# CPU_GPIOG_I_VDD.net
KiCad netlist of a schematic drawn in Altium Designer
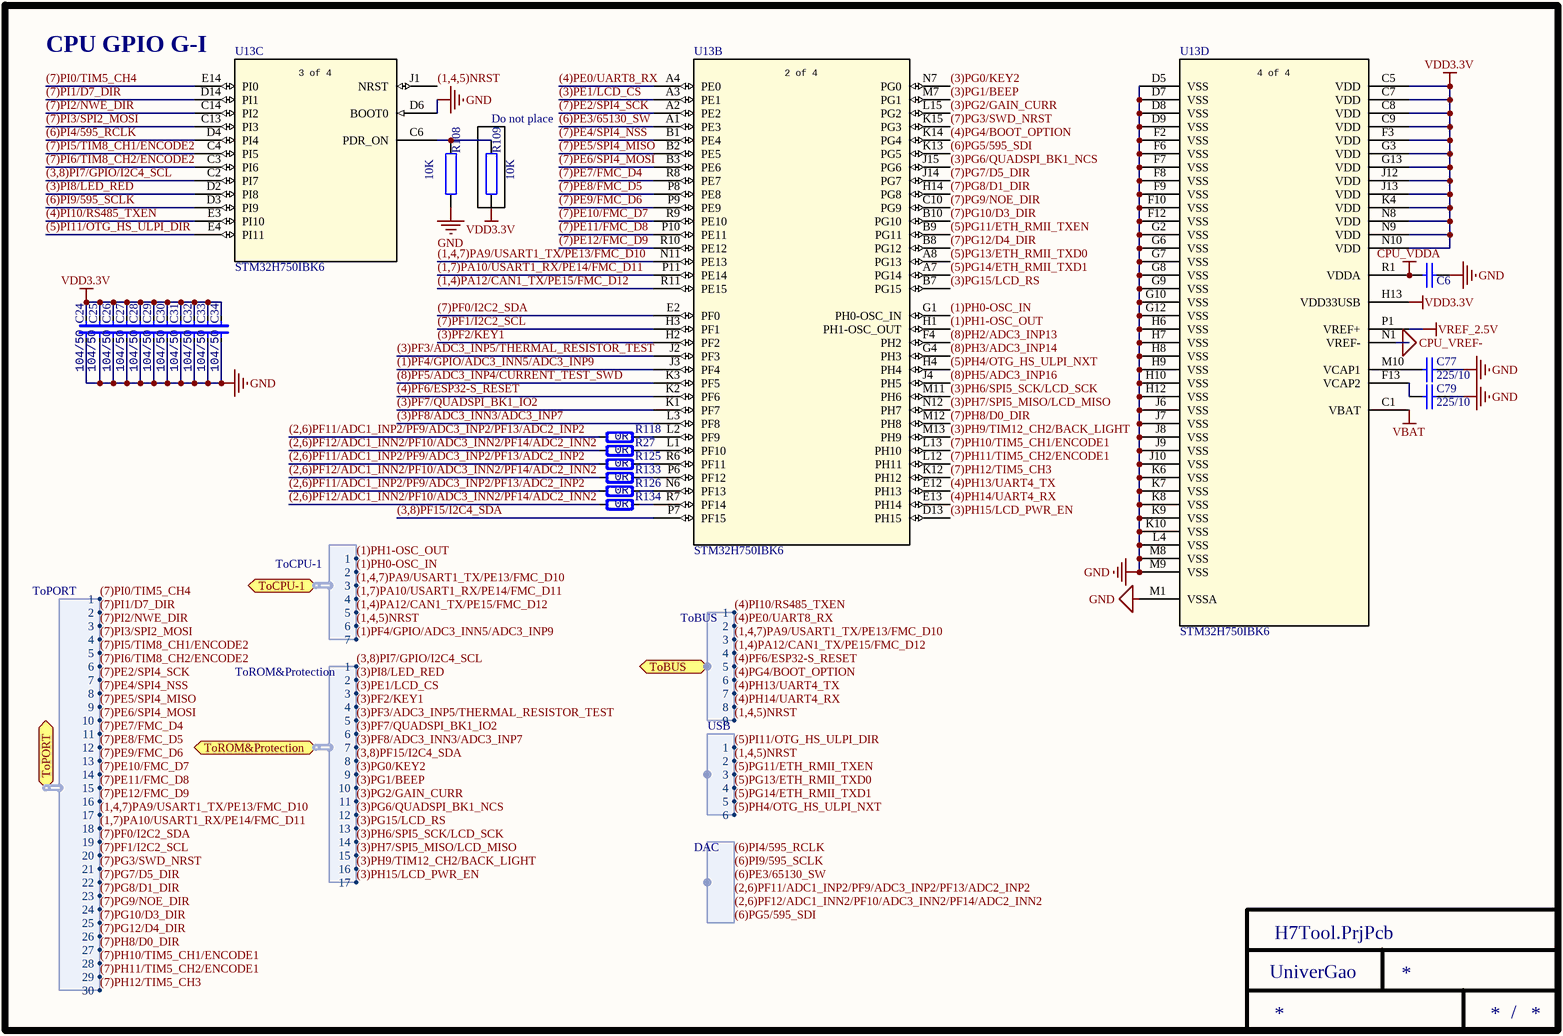
[diagram p0: CPU_GPIOG_I_VDD.SchDoc]

(export (version "E")
  (design (tool "Eeschema 10.0.6"))
  (components
    (comp (ref "C6") (value "104/50") (footprint "0603") (libsource (lib "电容") (part "CAP1")))
    (comp (ref "C24")
      (value "104/50")
      (footprint "PCB_PassiveCap:CAP_0603")
      (description "Capacitor")
      (fields (field (name "Comment") "C0603"))
      (libsource (lib "SCH_Passive") (part "Cap_0603"))
    )
    (comp (ref "C25")
      (value "104/50")
      (footprint "PCB_PassiveCap:CAP_0603")
      (description "Capacitor")
      (fields (field (name "Comment") "C0603"))
      (libsource (lib "SCH_Passive") (part "Cap_0603"))
    )
    (comp (ref "C26")
      (value "104/50")
      (footprint "PCB_PassiveCap:CAP_0603")
      (description "Capacitor")
      (fields (field (name "Comment") "C0603"))
      (libsource (lib "SCH_Passive") (part "Cap_0603"))
    )
    (comp (ref "C27")
      (value "104/50")
      (footprint "PCB_PassiveCap:CAP_0603")
      (description "Capacitor")
      (fields (field (name "Comment") "C0603"))
      (libsource (lib "SCH_Passive") (part "Cap_0603"))
    )
    (comp (ref "C28")
      (value "104/50")
      (footprint "PCB_PassiveCap:CAP_0603")
      (description "Capacitor")
      (fields (field (name "Comment") "C0603"))
      (libsource (lib "SCH_Passive") (part "Cap_0603"))
    )
    (comp (ref "C29")
      (value "104/50")
      (footprint "PCB_PassiveCap:CAP_0603")
      (description "Capacitor")
      (fields (field (name "Comment") "C0603"))
      (libsource (lib "SCH_Passive") (part "Cap_0603"))
    )
    (comp (ref "C30")
      (value "104/50")
      (footprint "PCB_PassiveCap:CAP_0603")
      (description "Capacitor")
      (fields (field (name "Comment") "C0603"))
      (libsource (lib "SCH_Passive") (part "Cap_0603"))
    )
    (comp (ref "C31")
      (value "104/50")
      (footprint "PCB_PassiveCap:CAP_0603")
      (description "Capacitor")
      (fields (field (name "Comment") "C0603"))
      (libsource (lib "SCH_Passive") (part "Cap_0603"))
    )
    (comp (ref "C32")
      (value "104/50")
      (footprint "PCB_PassiveCap:CAP_0603")
      (description "Capacitor")
      (fields (field (name "Comment") "C0603"))
      (libsource (lib "SCH_Passive") (part "Cap_0603"))
    )
    (comp (ref "C33")
      (value "104/50")
      (footprint "PCB_PassiveCap:CAP_0603")
      (description "Capacitor")
      (fields (field (name "Comment") "C0603"))
      (libsource (lib "SCH_Passive") (part "Cap_0603"))
    )
    (comp (ref "C34")
      (value "104/50")
      (footprint "PCB_PassiveCap:CAP_0603")
      (description "Capacitor")
      (fields (field (name "Comment") "C0603"))
      (libsource (lib "SCH_Passive") (part "Cap_0603"))
    )
    (comp (ref "C77") (value "225/10") (footprint "0603") (libsource (lib "电容") (part "CAP1")))
    (comp (ref "C79") (value "225/10") (footprint "0603") (libsource (lib "电容") (part "CAP1")))
    (comp (ref "R27")
      (value "0R")
      (footprint "PCB_PassiveRes:RES_0603")
      (description "Resistor")
      (fields (field (name "Comment") "R0603"))
      (libsource (lib "SCH_Passive") (part "Res_0603"))
    )
    (comp (ref "R108") (value "10K") (footprint "0603") (libsource (lib "电阻") (part "RES")))
    (comp (ref "R109")
      (value "10K")
      (footprint "0603")
      (description "10K(Do not place)")
      (libsource (lib "电阻") (part "RES"))
    )
    (comp (ref "R118")
      (value "0R")
      (footprint "PCB_PassiveRes:RES_0603")
      (description "Resistor")
      (fields (field (name "Comment") "R0603"))
      (libsource (lib "SCH_Passive") (part "Res_0603"))
    )
    (comp (ref "R125")
      (value "0R")
      (footprint "PCB_PassiveRes:RES_0603")
      (description "Resistor")
      (fields (field (name "Comment") "R0603"))
      (libsource (lib "SCH_Passive") (part "Res_0603"))
    )
    (comp (ref "R126")
      (value "0R")
      (footprint "PCB_PassiveRes:RES_0603")
      (description "Resistor")
      (fields (field (name "Comment") "R0603"))
      (libsource (lib "SCH_Passive") (part "Res_0603"))
    )
    (comp (ref "R133")
      (value "0R")
      (footprint "PCB_PassiveRes:RES_0603")
      (description "Resistor")
      (fields (field (name "Comment") "R0603"))
      (libsource (lib "SCH_Passive") (part "Res_0603"))
    )
    (comp (ref "R134")
      (value "0R")
      (footprint "PCB_PassiveRes:RES_0603")
      (description "Resistor")
      (fields (field (name "Comment") "R0603"))
      (libsource (lib "SCH_Passive") (part "Res_0603"))
    )
    (comp (ref "U13")
      (value "STM32H750IBK6")
      (footprint "UFBGA 10X10 P 0.65 176+25")
      (description "No Description Available")
      (fields (field (name "COPYRIGHT") "Copyright (C) 2022 Ultra Librarian. All rights reserved."))
      (libsource (lib "STM32H750IBK6") (part "STM32H750IBK6"))
    )
  )
  (nets
    (net (code "5") (name "/(1)PF4{slash}GPIO{slash}ADC3_INN5{slash}ADC3_INP9") (class "Default")
      (node (ref "U13") (pin "J3") (pinfunction "PF4_J3") (pintype "bidirectional"))
    )
    (net (code "6") (name "/(1)PH0-OSC_IN") (class "Default")
      (node (ref "U13") (pin "G1") (pinfunction "PH0-OSC_IN_G1") (pintype "bidirectional"))
    )
    (net (code "7") (name "/(1)PH1-OSC_OUT") (class "Default")
      (node (ref "U13") (pin "H1") (pinfunction "PH1-OSC_OUT_H1") (pintype "bidirectional"))
    )
    (net (code "8") (name "/(1,4)PA12{slash}CAN1_TX{slash}PE15{slash}FMC_D12") (class "Default")
      (node (ref "U13") (pin "R11") (pinfunction "PE15_R11") (pintype "bidirectional"))
    )
    (net (code "9") (name "/(1,4,5)NRST") (class "Default")
      (node (ref "U13") (pin "J1") (pinfunction "NRST_J1") (pintype "bidirectional"))
    )
    (net (code "10") (name "/(1,4,7)PA9{slash}USART1_TX{slash}PE13{slash}FMC_D10") (class "Default")
      (node (ref "U13") (pin "N11") (pinfunction "PE13_N11") (pintype "bidirectional"))
    )
    (net (code "11") (name "/(1,7)PA10{slash}USART1_RX{slash}PE14{slash}FMC_D11") (class "Default")
      (node (ref "U13") (pin "P11") (pinfunction "PE14_P11") (pintype "bidirectional"))
    )
    (net (code "12") (name "/(2,6)PF11{slash}ADC1_INP2{slash}PF9{slash}ADC3_INP2{slash}PF13{slash}ADC2_INP2") (class "Default")
      (node (ref "R118") (pin "1") (pinfunction "1_1") (pintype "passive"))
      (node (ref "R125") (pin "1") (pinfunction "1_1") (pintype "passive"))
      (node (ref "R126") (pin "1") (pinfunction "1_1") (pintype "passive"))
    )
    (net (code "13") (name "/(2,6)PF12{slash}ADC1_INN2{slash}PF10{slash}ADC3_INN2{slash}PF14{slash}ADC2_INN2") (class "Default")
      (node (ref "R133") (pin "1") (pinfunction "1_1") (pintype "passive"))
      (node (ref "R134") (pin "1") (pinfunction "1_1") (pintype "passive"))
      (node (ref "R27") (pin "1") (pinfunction "1_1") (pintype "passive"))
    )
    (net (code "14") (name "/(3)PE1{slash}LCD_CS") (class "Default")
      (node (ref "U13") (pin "A3") (pinfunction "PE1_A3") (pintype "bidirectional"))
    )
    (net (code "15") (name "/(3)PF2{slash}KEY1") (class "Default")
      (node (ref "U13") (pin "H2") (pinfunction "PF2_H2") (pintype "bidirectional"))
    )
    (net (code "16") (name "/(3)PF3{slash}ADC3_INP5{slash}THERMAL_RESISTOR_TEST") (class "Default")
      (node (ref "U13") (pin "J2") (pinfunction "PF3_J2") (pintype "bidirectional"))
    )
    (net (code "17") (name "/(3)PF7{slash}QUADSPI_BK1_IO2") (class "Default")
      (node (ref "U13") (pin "K1") (pinfunction "PF7_K1") (pintype "bidirectional"))
    )
    (net (code "18") (name "/(3)PF8{slash}ADC3_INN3{slash}ADC3_INP7") (class "Default")
      (node (ref "U13") (pin "L3") (pinfunction "PF8_L3") (pintype "bidirectional"))
    )
    (net (code "19") (name "/(3)PG0{slash}KEY2") (class "Default")
      (node (ref "U13") (pin "N7") (pinfunction "PG0_N7") (pintype "bidirectional"))
    )
    (net (code "20") (name "/(3)PG1{slash}BEEP") (class "Default")
      (node (ref "U13") (pin "M7") (pinfunction "PG1_M7") (pintype "bidirectional"))
    )
    (net (code "21") (name "/(3)PG2{slash}GAIN_CURR") (class "Default")
      (node (ref "U13") (pin "L15") (pinfunction "PG2_L15") (pintype "bidirectional"))
    )
    (net (code "22") (name "/(3)PG6{slash}QUADSPI_BK1_NCS") (class "Default")
      (node (ref "U13") (pin "J15") (pinfunction "PG6_J15") (pintype "bidirectional"))
    )
    (net (code "23") (name "/(3)PG15{slash}LCD_RS") (class "Default")
      (node (ref "U13") (pin "B7") (pinfunction "PG15_B7") (pintype "bidirectional"))
    )
    (net (code "24") (name "/(3)PH6{slash}SPI5_SCK{slash}LCD_SCK") (class "Default")
      (node (ref "U13") (pin "M11") (pinfunction "PH6_M11") (pintype "bidirectional"))
    )
    (net (code "25") (name "/(3)PH7{slash}SPI5_MISO{slash}LCD_MISO") (class "Default")
      (node (ref "U13") (pin "N12") (pinfunction "PH7_N12") (pintype "bidirectional"))
    )
    (net (code "26") (name "/(3)PH9{slash}TIM12_CH2{slash}BACK_LIGHT") (class "Default")
      (node (ref "U13") (pin "M13") (pinfunction "PH9_M13") (pintype "bidirectional"))
    )
    (net (code "27") (name "/(3)PH15{slash}LCD_PWR_EN") (class "Default")
      (node (ref "U13") (pin "D13") (pinfunction "PH15_D13") (pintype "bidirectional"))
    )
    (net (code "28") (name "/(3)PI8{slash}LED_RED") (class "Default")
      (node (ref "U13") (pin "D2") (pinfunction "PI8_D2") (pintype "bidirectional"))
    )
    (net (code "29") (name "/(3,8)PF15{slash}I2C4_SDA") (class "Default")
      (node (ref "U13") (pin "P7") (pinfunction "PF15_P7") (pintype "bidirectional"))
    )
    (net (code "30") (name "/(3,8)PI7{slash}GPIO{slash}I2C4_SCL") (class "Default")
      (node (ref "U13") (pin "C2") (pinfunction "PI7_C2") (pintype "bidirectional"))
    )
    (net (code "31") (name "/(4)PE0{slash}UART8_RX") (class "Default")
      (node (ref "U13") (pin "A4") (pinfunction "PE0_A4") (pintype "bidirectional"))
    )
    (net (code "32") (name "/(4)PF6{slash}ESP32-S_RESET") (class "Default")
      (node (ref "U13") (pin "K2") (pinfunction "PF6_K2") (pintype "bidirectional"))
    )
    (net (code "33") (name "/(4)PG4{slash}BOOT_OPTION") (class "Default")
      (node (ref "U13") (pin "K14") (pinfunction "PG4_K14") (pintype "bidirectional"))
    )
    (net (code "34") (name "/(4)PH13{slash}UART4_TX") (class "Default")
      (node (ref "U13") (pin "E12") (pinfunction "PH13_E12") (pintype "bidirectional"))
    )
    (net (code "35") (name "/(4)PH14{slash}UART4_RX") (class "Default")
      (node (ref "U13") (pin "E13") (pinfunction "PH14_E13") (pintype "bidirectional"))
    )
    (net (code "36") (name "/(4)PI10{slash}RS485_TXEN") (class "Default")
      (node (ref "U13") (pin "E3") (pinfunction "PI10_E3") (pintype "bidirectional"))
    )
    (net (code "37") (name "/(5)PG11{slash}ETH_RMII_TXEN") (class "Default")
      (node (ref "U13") (pin "B9") (pinfunction "PG11_B9") (pintype "bidirectional"))
    )
    (net (code "38") (name "/(5)PG13{slash}ETH_RMII_TXD0") (class "Default")
      (node (ref "U13") (pin "A8") (pinfunction "PG13_A8") (pintype "bidirectional"))
    )
    (net (code "39") (name "/(5)PG14{slash}ETH_RMII_TXD1") (class "Default")
      (node (ref "U13") (pin "A7") (pinfunction "PG14_A7") (pintype "bidirectional"))
    )
    (net (code "40") (name "/(5)PH4{slash}OTG_HS_ULPI_NXT") (class "Default")
      (node (ref "U13") (pin "H4") (pinfunction "PH4_H4") (pintype "bidirectional"))
    )
    (net (code "41") (name "/(5)PI11{slash}OTG_HS_ULPI_DIR") (class "Default")
      (node (ref "U13") (pin "E4") (pinfunction "PI11_E4") (pintype "bidirectional"))
    )
    (net (code "42") (name "/(6)PE3{slash}65130_SW") (class "Default")
      (node (ref "U13") (pin "A1") (pinfunction "PE3_A1") (pintype "bidirectional"))
    )
    (net (code "43") (name "/(6)PG5{slash}595_SDI") (class "Default")
      (node (ref "U13") (pin "K13") (pinfunction "PG5_K13") (pintype "bidirectional"))
    )
    (net (code "44") (name "/(6)PI4{slash}595_RCLK") (class "Default")
      (node (ref "U13") (pin "D4") (pinfunction "PI4_D4") (pintype "bidirectional"))
    )
    (net (code "45") (name "/(6)PI9{slash}595_SCLK") (class "Default")
      (node (ref "U13") (pin "D3") (pinfunction "PI9_D3") (pintype "bidirectional"))
    )
    (net (code "46") (name "/(7)PE2{slash}SPI4_SCK") (class "Default")
      (node (ref "U13") (pin "A2") (pinfunction "PE2_A2") (pintype "bidirectional"))
    )
    (net (code "47") (name "/(7)PE4{slash}SPI4_NSS") (class "Default")
      (node (ref "U13") (pin "B1") (pinfunction "PE4_B1") (pintype "bidirectional"))
    )
    (net (code "48") (name "/(7)PE5{slash}SPI4_MISO") (class "Default")
      (node (ref "U13") (pin "B2") (pinfunction "PE5_B2") (pintype "bidirectional"))
    )
    (net (code "49") (name "/(7)PE6{slash}SPI4_MOSI") (class "Default")
      (node (ref "U13") (pin "B3") (pinfunction "PE6_B3") (pintype "bidirectional"))
    )
    (net (code "50") (name "/(7)PE7{slash}FMC_D4") (class "Default")
      (node (ref "U13") (pin "R8") (pinfunction "PE7_R8") (pintype "bidirectional"))
    )
    (net (code "51") (name "/(7)PE8{slash}FMC_D5") (class "Default")
      (node (ref "U13") (pin "P8") (pinfunction "PE8_P8") (pintype "bidirectional"))
    )
    (net (code "52") (name "/(7)PE9{slash}FMC_D6") (class "Default")
      (node (ref "U13") (pin "P9") (pinfunction "PE9_P9") (pintype "bidirectional"))
    )
    (net (code "53") (name "/(7)PE10{slash}FMC_D7") (class "Default")
      (node (ref "U13") (pin "R9") (pinfunction "PE10_R9") (pintype "bidirectional"))
    )
    (net (code "54") (name "/(7)PE11{slash}FMC_D8") (class "Default")
      (node (ref "U13") (pin "P10") (pinfunction "PE11_P10") (pintype "bidirectional"))
    )
    (net (code "55") (name "/(7)PE12{slash}FMC_D9") (class "Default")
      (node (ref "U13") (pin "R10") (pinfunction "PE12_R10") (pintype "bidirectional"))
    )
    (net (code "56") (name "/(7)PF0{slash}I2C2_SDA") (class "Default")
      (node (ref "U13") (pin "E2") (pinfunction "PF0_E2") (pintype "bidirectional"))
    )
    (net (code "57") (name "/(7)PF1{slash}I2C2_SCL") (class "Default")
      (node (ref "U13") (pin "H3") (pinfunction "PF1_H3") (pintype "bidirectional"))
    )
    (net (code "58") (name "/(7)PG3{slash}SWD_NRST") (class "Default")
      (node (ref "U13") (pin "K15") (pinfunction "PG3_K15") (pintype "bidirectional"))
    )
    (net (code "59") (name "/(7)PG7{slash}D5_DIR") (class "Default")
      (node (ref "U13") (pin "J14") (pinfunction "PG7_J14") (pintype "bidirectional"))
    )
    (net (code "60") (name "/(7)PG8{slash}D1_DIR") (class "Default")
      (node (ref "U13") (pin "H14") (pinfunction "PG8_H14") (pintype "bidirectional"))
    )
    (net (code "61") (name "/(7)PG9{slash}NOE_DIR") (class "Default")
      (node (ref "U13") (pin "C10") (pinfunction "PG9_C10") (pintype "bidirectional"))
    )
    (net (code "62") (name "/(7)PG10{slash}D3_DIR") (class "Default")
      (node (ref "U13") (pin "B10") (pinfunction "PG10_B10") (pintype "bidirectional"))
    )
    (net (code "63") (name "/(7)PG12{slash}D4_DIR") (class "Default")
      (node (ref "U13") (pin "B8") (pinfunction "PG12_B8") (pintype "bidirectional"))
    )
    (net (code "64") (name "/(7)PH8{slash}D0_DIR") (class "Default")
      (node (ref "U13") (pin "M12") (pinfunction "PH8_M12") (pintype "bidirectional"))
    )
    (net (code "65") (name "/(7)PH10{slash}TIM5_CH1{slash}ENCODE1") (class "Default")
      (node (ref "U13") (pin "L13") (pinfunction "PH10_L13") (pintype "bidirectional"))
    )
    (net (code "66") (name "/(7)PH11{slash}TIM5_CH2{slash}ENCODE1") (class "Default")
      (node (ref "U13") (pin "L12") (pinfunction "PH11_L12") (pintype "bidirectional"))
    )
    (net (code "67") (name "/(7)PH12{slash}TIM5_CH3") (class "Default")
      (node (ref "U13") (pin "K12") (pinfunction "PH12_K12") (pintype "bidirectional"))
    )
    (net (code "68") (name "/(7)PI0{slash}TIM5_CH4") (class "Default")
      (node (ref "U13") (pin "E14") (pinfunction "PI0_E14") (pintype "bidirectional"))
    )
    (net (code "69") (name "/(7)PI1{slash}D7_DIR") (class "Default")
      (node (ref "U13") (pin "D14") (pinfunction "PI1_D14") (pintype "bidirectional"))
    )
    (net (code "70") (name "/(7)PI2{slash}NWE_DIR") (class "Default")
      (node (ref "U13") (pin "C14") (pinfunction "PI2_C14") (pintype "bidirectional"))
    )
    (net (code "71") (name "/(7)PI3{slash}SPI2_MOSI") (class "Default")
      (node (ref "U13") (pin "C13") (pinfunction "PI3_C13") (pintype "bidirectional"))
    )
    (net (code "72") (name "/(7)PI5{slash}TIM8_CH1{slash}ENCODE2") (class "Default")
      (node (ref "U13") (pin "C4") (pinfunction "PI5_C4") (pintype "bidirectional"))
    )
    (net (code "73") (name "/(7)PI6{slash}TIM8_CH2{slash}ENCODE2") (class "Default")
      (node (ref "U13") (pin "C3") (pinfunction "PI6_C3") (pintype "bidirectional"))
    )
    (net (code "74") (name "/(8)PF5{slash}ADC3_INP4{slash}CURRENT_TEST_SWD") (class "Default")
      (node (ref "U13") (pin "K3") (pinfunction "PF5_K3") (pintype "bidirectional"))
    )
    (net (code "75") (name "/(8)PH2{slash}ADC3_INP13") (class "Default")
      (node (ref "U13") (pin "F4") (pinfunction "PH2_F4") (pintype "bidirectional"))
    )
    (net (code "76") (name "/(8)PH3{slash}ADC3_INP14") (class "Default")
      (node (ref "U13") (pin "G4") (pinfunction "PH3_G4") (pintype "bidirectional"))
    )
    (net (code "77") (name "/(8)PH5{slash}ADC3_INP16") (class "Default")
      (node (ref "U13") (pin "J4") (pinfunction "PH5_J4") (pintype "bidirectional"))
    )
    (net (code "82") (name "CPU_VDDA") (class "Default")
      (node (ref "C6") (pin "2") (pinfunction "2_2") (pintype "passive"))
      (node (ref "U13") (pin "R1") (pinfunction "VDDA_R1") (pintype "power_in"))
    )
    (net (code "83") (name "CPU_VREF-") (class "Default")
      (node (ref "U13") (pin "N1") (pinfunction "VREF-_N1") (pintype "power_in"))
    )
    (net (code "84") (name "GND") (class "Default")
      (node (ref "C24") (pin "1") (pinfunction "1_1") (pintype "passive"))
      (node (ref "C25") (pin "1") (pinfunction "1_1") (pintype "passive"))
      (node (ref "C26") (pin "1") (pinfunction "1_1") (pintype "passive"))
      (node (ref "C27") (pin "1") (pinfunction "1_1") (pintype "passive"))
      (node (ref "C28") (pin "1") (pinfunction "1_1") (pintype "passive"))
      (node (ref "C29") (pin "1") (pinfunction "1_1") (pintype "passive"))
      (node (ref "C30") (pin "1") (pinfunction "1_1") (pintype "passive"))
      (node (ref "C31") (pin "1") (pinfunction "1_1") (pintype "passive"))
      (node (ref "C32") (pin "1") (pinfunction "1_1") (pintype "passive"))
      (node (ref "C33") (pin "1") (pinfunction "1_1") (pintype "passive"))
      (node (ref "C34") (pin "1") (pinfunction "1_1") (pintype "passive"))
      (node (ref "C6") (pin "1") (pinfunction "1_1") (pintype "passive"))
      (node (ref "C77") (pin "1") (pinfunction "1_1") (pintype "passive"))
      (node (ref "C79") (pin "1") (pinfunction "1_1") (pintype "passive"))
      (node (ref "R108") (pin "2") (pinfunction "2_2") (pintype "passive"))
      (node (ref "U13") (pin "D5") (pinfunction "VSS_D5") (pintype "power_in"))
      (node (ref "U13") (pin "D6") (pinfunction "BOOT0_D6") (pintype "input"))
      (node (ref "U13") (pin "D7") (pinfunction "VSS_D7") (pintype "power_in"))
      (node (ref "U13") (pin "D8") (pinfunction "VSS_D8") (pintype "power_in"))
      (node (ref "U13") (pin "D9") (pinfunction "VSS_D9") (pintype "power_in"))
      (node (ref "U13") (pin "F10") (pinfunction "VSS_F10") (pintype "power_in"))
      (node (ref "U13") (pin "F12") (pinfunction "VSS_F12") (pintype "power_in"))
      (node (ref "U13") (pin "F2") (pinfunction "VSS_F2") (pintype "power_in"))
      (node (ref "U13") (pin "F6") (pinfunction "VSS_F6") (pintype "power_in"))
      (node (ref "U13") (pin "F7") (pinfunction "VSS_F7") (pintype "power_in"))
      (node (ref "U13") (pin "F8") (pinfunction "VSS_F8") (pintype "power_in"))
      (node (ref "U13") (pin "F9") (pinfunction "VSS_F9") (pintype "power_in"))
      (node (ref "U13") (pin "G10") (pinfunction "VSS_G10") (pintype "power_in"))
      (node (ref "U13") (pin "G12") (pinfunction "VSS_G12") (pintype "power_in"))
      (node (ref "U13") (pin "G2") (pinfunction "VSS_G2") (pintype "power_in"))
      (node (ref "U13") (pin "G6") (pinfunction "VSS_G6") (pintype "power_in"))
      (node (ref "U13") (pin "G7") (pinfunction "VSS_G7") (pintype "power_in"))
      (node (ref "U13") (pin "G8") (pinfunction "VSS_G8") (pintype "power_in"))
      (node (ref "U13") (pin "G9") (pinfunction "VSS_G9") (pintype "power_in"))
      (node (ref "U13") (pin "H10") (pinfunction "VSS_H10") (pintype "power_in"))
      (node (ref "U13") (pin "H12") (pinfunction "VSS_H12") (pintype "power_in"))
      (node (ref "U13") (pin "H6") (pinfunction "VSS_H6") (pintype "power_in"))
      (node (ref "U13") (pin "H7") (pinfunction "VSS_H7") (pintype "power_in"))
      (node (ref "U13") (pin "H8") (pinfunction "VSS_H8") (pintype "power_in"))
      (node (ref "U13") (pin "H9") (pinfunction "VSS_H9") (pintype "power_in"))
      (node (ref "U13") (pin "J10") (pinfunction "VSS_J10") (pintype "power_in"))
      (node (ref "U13") (pin "J6") (pinfunction "VSS_J6") (pintype "power_in"))
      (node (ref "U13") (pin "J7") (pinfunction "VSS_J7") (pintype "power_in"))
      (node (ref "U13") (pin "J8") (pinfunction "VSS_J8") (pintype "power_in"))
      (node (ref "U13") (pin "J9") (pinfunction "VSS_J9") (pintype "power_in"))
      (node (ref "U13") (pin "K10") (pinfunction "VSS_K10") (pintype "power_in"))
      (node (ref "U13") (pin "K6") (pinfunction "VSS_K6") (pintype "power_in"))
      (node (ref "U13") (pin "K7") (pinfunction "VSS_K7") (pintype "power_in"))
      (node (ref "U13") (pin "K8") (pinfunction "VSS_K8") (pintype "power_in"))
      (node (ref "U13") (pin "K9") (pinfunction "VSS_K9") (pintype "power_in"))
      (node (ref "U13") (pin "L4") (pinfunction "VSS_L4") (pintype "power_in"))
      (node (ref "U13") (pin "M1") (pinfunction "VSSA_M1") (pintype "power_in"))
      (node (ref "U13") (pin "M8") (pinfunction "VSS_M8") (pintype "power_in"))
      (node (ref "U13") (pin "M9") (pinfunction "VSS_M9") (pintype "power_in"))
    )
    (net (code "85") (name "Net-(U13B-PF9)") (class "Default")
      (node (ref "R118") (pin "2") (pinfunction "2_2") (pintype "passive"))
      (node (ref "U13") (pin "L2") (pinfunction "PF9_L2") (pintype "bidirectional"))
    )
    (net (code "86") (name "Net-(U13B-PF10)") (class "Default")
      (node (ref "R27") (pin "2") (pinfunction "2_2") (pintype "passive"))
      (node (ref "U13") (pin "L1") (pinfunction "PF10_L1") (pintype "bidirectional"))
    )
    (net (code "87") (name "Net-(U13B-PF11)") (class "Default")
      (node (ref "R125") (pin "2") (pinfunction "2_2") (pintype "passive"))
      (node (ref "U13") (pin "R6") (pinfunction "PF11_R6") (pintype "bidirectional"))
    )
    (net (code "88") (name "Net-(U13B-PF12)") (class "Default")
      (node (ref "R133") (pin "2") (pinfunction "2_2") (pintype "passive"))
      (node (ref "U13") (pin "P6") (pinfunction "PF12_P6") (pintype "bidirectional"))
    )
    (net (code "89") (name "Net-(U13B-PF13)") (class "Default")
      (node (ref "R126") (pin "2") (pinfunction "2_2") (pintype "passive"))
      (node (ref "U13") (pin "N6") (pinfunction "PF13_N6") (pintype "bidirectional"))
    )
    (net (code "90") (name "Net-(U13B-PF14)") (class "Default")
      (node (ref "R134") (pin "2") (pinfunction "2_2") (pintype "passive"))
      (node (ref "U13") (pin "R7") (pinfunction "PF14_R7") (pintype "bidirectional"))
    )
    (net (code "91") (name "Net-(U13C-PDR_ON)") (class "Default")
      (node (ref "R108") (pin "1") (pinfunction "1_1") (pintype "passive"))
      (node (ref "R109") (pin "1") (pinfunction "1_1") (pintype "passive"))
      (node (ref "U13") (pin "C6") (pinfunction "PDR_ON_C6") (pintype "passive"))
    )
    (net (code "92") (name "Net-(U13D-VCAP1)") (class "Default")
      (node (ref "C77") (pin "2") (pinfunction "2_2") (pintype "passive"))
      (node (ref "U13") (pin "M10") (pinfunction "VCAP1_M10") (pintype "power_in"))
    )
    (net (code "93") (name "Net-(U13D-VCAP2)") (class "Default")
      (node (ref "C79") (pin "2") (pinfunction "2_2") (pintype "passive"))
      (node (ref "U13") (pin "F13") (pinfunction "VCAP2_F13") (pintype "power_in"))
    )
    (net (code "94") (name "VBAT") (class "Default")
      (node (ref "U13") (pin "C1") (pinfunction "VBAT_C1") (pintype "power_in"))
    )
    (net (code "95") (name "VDD3.3V") (class "Default")
      (node (ref "C24") (pin "2") (pinfunction "2_2") (pintype "passive"))
      (node (ref "C25") (pin "2") (pinfunction "2_2") (pintype "passive"))
      (node (ref "C26") (pin "2") (pinfunction "2_2") (pintype "passive"))
      (node (ref "C27") (pin "2") (pinfunction "2_2") (pintype "passive"))
      (node (ref "C28") (pin "2") (pinfunction "2_2") (pintype "passive"))
      (node (ref "C29") (pin "2") (pinfunction "2_2") (pintype "passive"))
      (node (ref "C30") (pin "2") (pinfunction "2_2") (pintype "passive"))
      (node (ref "C31") (pin "2") (pinfunction "2_2") (pintype "passive"))
      (node (ref "C32") (pin "2") (pinfunction "2_2") (pintype "passive"))
      (node (ref "C33") (pin "2") (pinfunction "2_2") (pintype "passive"))
      (node (ref "C34") (pin "2") (pinfunction "2_2") (pintype "passive"))
      (node (ref "R109") (pin "2") (pinfunction "2_2") (pintype "passive"))
      (node (ref "U13") (pin "C5") (pinfunction "VDD_C5") (pintype "power_in"))
      (node (ref "U13") (pin "C7") (pinfunction "VDD_C7") (pintype "power_in"))
      (node (ref "U13") (pin "C8") (pinfunction "VDD_C8") (pintype "power_in"))
      (node (ref "U13") (pin "C9") (pinfunction "VDD_C9") (pintype "power_in"))
      (node (ref "U13") (pin "F3") (pinfunction "VDD_F3") (pintype "power_in"))
      (node (ref "U13") (pin "G13") (pinfunction "VDD_G13") (pintype "power_in"))
      (node (ref "U13") (pin "G3") (pinfunction "VDD_G3") (pintype "power_in"))
      (node (ref "U13") (pin "H13") (pinfunction "VDD33USB_H13") (pintype "power_in"))
      (node (ref "U13") (pin "J12") (pinfunction "VDD_J12") (pintype "power_in"))
      (node (ref "U13") (pin "J13") (pinfunction "VDD_J13") (pintype "power_in"))
      (node (ref "U13") (pin "K4") (pinfunction "VDD_K4") (pintype "power_in"))
      (node (ref "U13") (pin "N10") (pinfunction "VDD_N10") (pintype "power_in"))
      (node (ref "U13") (pin "N8") (pinfunction "VDD_N8") (pintype "power_in"))
      (node (ref "U13") (pin "N9") (pinfunction "VDD_N9") (pintype "power_in"))
    )
    (net (code "96") (name "VREF_2.5V") (class "Default")
      (node (ref "U13") (pin "P1") (pinfunction "VREF+_P1") (pintype "power_in"))
    )
  )
)
